# PWM_BoardSchem.net
KiCad netlist of a schematic drawn in Altium Designer
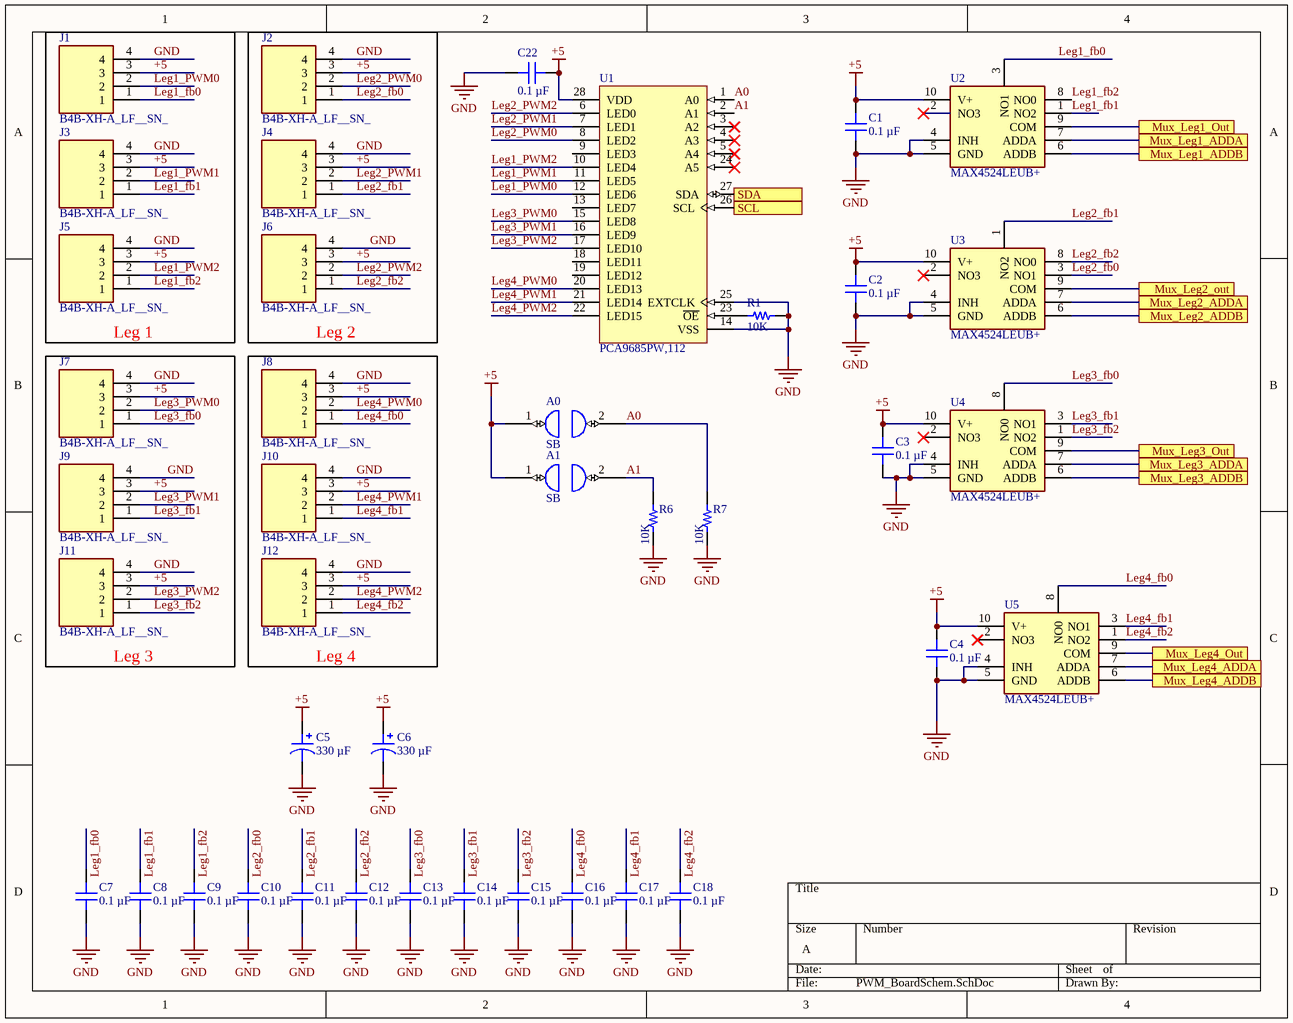
[diagram p0: PWM_BoardSchem.SchDoc]

(export (version "E")
  (design (tool "Eeschema 10.0.6"))
  (components
    (comp (ref "A0")
      (value "SB")
      (footprint "CAPC2010X06N")
      (description "Solder Bridge/0 ohm")
      (libsource (lib "Donados") (part "SB-Symbol-1"))
    )
    (comp (ref "A1")
      (value "SB")
      (footprint "CAPC2010X06N")
      (description "Solder Bridge/0 ohm")
      (libsource (lib "Donados") (part "SB-Symbol-1"))
    )
    (comp (ref "C1")
      (value "0.1 µF")
      (footprint "CAP 1206_3216 - 0.8MM")
      (description "CAP CER 0.1UF 50V Y5V 1206")
      (fields (field (name "PART NUMBER") "CC1206ZRY5V9BB104") (field (name "MANUFACTURER") "Yageo"))
      (libsource (lib "Celestial Altium Library - altium_library") (part "Capacitor"))
    )
    (comp (ref "C2")
      (value "0.1 µF")
      (footprint "CAP 1206_3216 - 0.8MM")
      (description "CAP CER 0.1UF 50V Y5V 1206")
      (fields (field (name "PART NUMBER") "CC1206ZRY5V9BB104") (field (name "MANUFACTURER") "Yageo"))
      (libsource (lib "Celestial Altium Library - altium_library") (part "Capacitor"))
    )
    (comp (ref "C3")
      (value "0.1 µF")
      (footprint "CAP 1206_3216 - 0.8MM")
      (description "CAP CER 0.1UF 50V Y5V 1206")
      (fields (field (name "PART NUMBER") "CC1206ZRY5V9BB104") (field (name "MANUFACTURER") "Yageo"))
      (libsource (lib "Celestial Altium Library - altium_library") (part "Capacitor"))
    )
    (comp (ref "C4")
      (value "0.1 µF")
      (footprint "CAP 1206_3216 - 0.8MM")
      (description "CAP CER 0.1UF 50V Y5V 1206")
      (fields (field (name "PART NUMBER") "CC1206ZRY5V9BB104") (field (name "MANUFACTURER") "Yageo"))
      (libsource (lib "Celestial Altium Library - altium_library") (part "Capacitor"))
    )
    (comp (ref "C5")
      (value "330 µF")
      (footprint "CAP TH ALPOLY D8.00mm S3.50mm H9.00mm")
      (description "CAP ALUM POLY 330UF 20% 16V T/H")
      (fields (field (name "PART NUMBER") "RL81C331MDN1KX") (field (name "MANUFACTURER") "Nichicon"))
      (libsource (lib "Celestial Altium Library - altium_library") (part "Polarised Capacitor"))
    )
    (comp (ref "C6")
      (value "330 µF")
      (footprint "CAP TH ALPOLY D8.00mm S3.50mm H9.00mm")
      (description "CAP ALUM POLY 330UF 20% 16V T/H")
      (fields (field (name "PART NUMBER") "RL81C331MDN1KX") (field (name "MANUFACTURER") "Nichicon"))
      (libsource (lib "Celestial Altium Library - altium_library") (part "Polarised Capacitor"))
    )
    (comp (ref "C7")
      (value "0.1 µF")
      (footprint "CAP 1206_3216 - 0.8MM")
      (description "CAP CER 0.1UF 50V Y5V 1206")
      (fields (field (name "PART NUMBER") "CC1206ZRY5V9BB104") (field (name "MANUFACTURER") "Yageo"))
      (libsource (lib "Celestial Altium Library - altium_library") (part "Capacitor"))
    )
    (comp (ref "C8")
      (value "0.1 µF")
      (footprint "CAP 1206_3216 - 0.8MM")
      (description "CAP CER 0.1UF 50V Y5V 1206")
      (fields (field (name "PART NUMBER") "CC1206ZRY5V9BB104") (field (name "MANUFACTURER") "Yageo"))
      (libsource (lib "Celestial Altium Library - altium_library") (part "Capacitor"))
    )
    (comp (ref "C9")
      (value "0.1 µF")
      (footprint "CAP 1206_3216 - 0.8MM")
      (description "CAP CER 0.1UF 50V Y5V 1206")
      (fields (field (name "PART NUMBER") "CC1206ZRY5V9BB104") (field (name "MANUFACTURER") "Yageo"))
      (libsource (lib "Celestial Altium Library - altium_library") (part "Capacitor"))
    )
    (comp (ref "C10")
      (value "0.1 µF")
      (footprint "CAP 1206_3216 - 0.8MM")
      (description "CAP CER 0.1UF 50V Y5V 1206")
      (fields (field (name "PART NUMBER") "CC1206ZRY5V9BB104") (field (name "MANUFACTURER") "Yageo"))
      (libsource (lib "Celestial Altium Library - altium_library") (part "Capacitor"))
    )
    (comp (ref "C11")
      (value "0.1 µF")
      (footprint "CAP 1206_3216 - 0.8MM")
      (description "CAP CER 0.1UF 50V Y5V 1206")
      (fields (field (name "PART NUMBER") "CC1206ZRY5V9BB104") (field (name "MANUFACTURER") "Yageo"))
      (libsource (lib "Celestial Altium Library - altium_library") (part "Capacitor"))
    )
    (comp (ref "C12")
      (value "0.1 µF")
      (footprint "CAP 1206_3216 - 0.8MM")
      (description "CAP CER 0.1UF 50V Y5V 1206")
      (fields (field (name "PART NUMBER") "CC1206ZRY5V9BB104") (field (name "MANUFACTURER") "Yageo"))
      (libsource (lib "Celestial Altium Library - altium_library") (part "Capacitor"))
    )
    (comp (ref "C13")
      (value "0.1 µF")
      (footprint "CAP 1206_3216 - 0.8MM")
      (description "CAP CER 0.1UF 50V Y5V 1206")
      (fields (field (name "PART NUMBER") "CC1206ZRY5V9BB104") (field (name "MANUFACTURER") "Yageo"))
      (libsource (lib "Celestial Altium Library - altium_library") (part "Capacitor"))
    )
    (comp (ref "C14")
      (value "0.1 µF")
      (footprint "CAP 1206_3216 - 0.8MM")
      (description "CAP CER 0.1UF 50V Y5V 1206")
      (fields (field (name "PART NUMBER") "CC1206ZRY5V9BB104") (field (name "MANUFACTURER") "Yageo"))
      (libsource (lib "Celestial Altium Library - altium_library") (part "Capacitor"))
    )
    (comp (ref "C15")
      (value "0.1 µF")
      (footprint "CAP 1206_3216 - 0.8MM")
      (description "CAP CER 0.1UF 50V Y5V 1206")
      (fields (field (name "PART NUMBER") "CC1206ZRY5V9BB104") (field (name "MANUFACTURER") "Yageo"))
      (libsource (lib "Celestial Altium Library - altium_library") (part "Capacitor"))
    )
    (comp (ref "C16")
      (value "0.1 µF")
      (footprint "CAP 1206_3216 - 0.8MM")
      (description "CAP CER 0.1UF 50V Y5V 1206")
      (fields (field (name "PART NUMBER") "CC1206ZRY5V9BB104") (field (name "MANUFACTURER") "Yageo"))
      (libsource (lib "Celestial Altium Library - altium_library") (part "Capacitor"))
    )
    (comp (ref "C17")
      (value "0.1 µF")
      (footprint "CAP 1206_3216 - 0.8MM")
      (description "CAP CER 0.1UF 50V Y5V 1206")
      (fields (field (name "PART NUMBER") "CC1206ZRY5V9BB104") (field (name "MANUFACTURER") "Yageo"))
      (libsource (lib "Celestial Altium Library - altium_library") (part "Capacitor"))
    )
    (comp (ref "C18")
      (value "0.1 µF")
      (footprint "CAP 1206_3216 - 0.8MM")
      (description "CAP CER 0.1UF 50V Y5V 1206")
      (fields (field (name "PART NUMBER") "CC1206ZRY5V9BB104") (field (name "MANUFACTURER") "Yageo"))
      (libsource (lib "Celestial Altium Library - altium_library") (part "Capacitor"))
    )
    (comp (ref "C22")
      (value "0.1 µF")
      (footprint "CAP 1206_3216 - 0.8MM")
      (description "CAP CER 0.1UF 50V Y5V 1206")
      (fields (field (name "PART NUMBER") "CC1206ZRY5V9BB104") (field (name "MANUFACTURER") "Yageo"))
      (libsource (lib "Celestial Altium Library - altium_library") (part "Capacitor"))
    )
    (comp (ref "J1")
      (value "B4B-XH-A_LF__SN_")
      (footprint "SamacSys:B4BXHALFSN")
      (description "Connector")
      (fields (field (name "MANUFACTURER_PART_NUMBER") "B4B-XH-A(LF)(SN)"))
      (libsource (lib "*") (part "B4B-XH-A_LF__SN_"))
    )
    (comp (ref "J2")
      (value "B4B-XH-A_LF__SN_")
      (footprint "SamacSys:B4BXHALFSN")
      (description "Connector")
      (fields (field (name "MANUFACTURER_PART_NUMBER") "B4B-XH-A(LF)(SN)"))
      (libsource (lib "*") (part "B4B-XH-A_LF__SN_"))
    )
    (comp (ref "J3")
      (value "B4B-XH-A_LF__SN_")
      (footprint "SamacSys:B4BXHALFSN")
      (description "Connector")
      (fields (field (name "MANUFACTURER_PART_NUMBER") "B4B-XH-A(LF)(SN)"))
      (libsource (lib "*") (part "B4B-XH-A_LF__SN_"))
    )
    (comp (ref "J4")
      (value "B4B-XH-A_LF__SN_")
      (footprint "SamacSys:B4BXHALFSN")
      (description "Connector")
      (fields (field (name "MANUFACTURER_PART_NUMBER") "B4B-XH-A(LF)(SN)"))
      (libsource (lib "*") (part "B4B-XH-A_LF__SN_"))
    )
    (comp (ref "J5")
      (value "B4B-XH-A_LF__SN_")
      (footprint "SamacSys:B4BXHALFSN")
      (description "Connector")
      (fields (field (name "MANUFACTURER_PART_NUMBER") "B4B-XH-A(LF)(SN)"))
      (libsource (lib "*") (part "B4B-XH-A_LF__SN_"))
    )
    (comp (ref "J6")
      (value "B4B-XH-A_LF__SN_")
      (footprint "SamacSys:B4BXHALFSN")
      (description "Connector")
      (fields (field (name "MANUFACTURER_PART_NUMBER") "B4B-XH-A(LF)(SN)"))
      (libsource (lib "*") (part "B4B-XH-A_LF__SN_"))
    )
    (comp (ref "J7")
      (value "B4B-XH-A_LF__SN_")
      (footprint "SamacSys:B4BXHALFSN")
      (description "Connector")
      (fields (field (name "MANUFACTURER_PART_NUMBER") "B4B-XH-A(LF)(SN)"))
      (libsource (lib "*") (part "B4B-XH-A_LF__SN_"))
    )
    (comp (ref "J8")
      (value "B4B-XH-A_LF__SN_")
      (footprint "SamacSys:B4BXHALFSN")
      (description "Connector")
      (fields (field (name "MANUFACTURER_PART_NUMBER") "B4B-XH-A(LF)(SN)"))
      (libsource (lib "*") (part "B4B-XH-A_LF__SN_"))
    )
    (comp (ref "J9")
      (value "B4B-XH-A_LF__SN_")
      (footprint "SamacSys:B4BXHALFSN")
      (description "Connector")
      (fields (field (name "MANUFACTURER_PART_NUMBER") "B4B-XH-A(LF)(SN)"))
      (libsource (lib "*") (part "B4B-XH-A_LF__SN_"))
    )
    (comp (ref "J10")
      (value "B4B-XH-A_LF__SN_")
      (footprint "SamacSys:B4BXHALFSN")
      (description "Connector")
      (fields (field (name "MANUFACTURER_PART_NUMBER") "B4B-XH-A(LF)(SN)"))
      (libsource (lib "*") (part "B4B-XH-A_LF__SN_"))
    )
    (comp (ref "J11")
      (value "B4B-XH-A_LF__SN_")
      (footprint "SamacSys:B4BXHALFSN")
      (description "Connector")
      (fields (field (name "MANUFACTURER_PART_NUMBER") "B4B-XH-A(LF)(SN)"))
      (libsource (lib "*") (part "B4B-XH-A_LF__SN_"))
    )
    (comp (ref "J12")
      (value "B4B-XH-A_LF__SN_")
      (footprint "SamacSys:B4BXHALFSN")
      (description "Connector")
      (fields (field (name "MANUFACTURER_PART_NUMBER") "B4B-XH-A(LF)(SN)"))
      (libsource (lib "*") (part "B4B-XH-A_LF__SN_"))
    )
    (comp (ref "R1")
      (value "10K")
      (footprint "RES 1206_3216")
      (description "RES SMD 10K OHM 1% 1/2W 1206")
      (fields (field (name "PART NUMBER") "ESR18EZPF1002") (field (name "MANUFACTURER") "Rohm Semiconductor"))
      (libsource (lib "Celestial Altium Library - altium_library") (part "Resistor"))
    )
    (comp (ref "R6")
      (value "10K")
      (footprint "RES 1206_3216")
      (description "RES SMD 10K OHM 1% 1/2W 1206")
      (fields (field (name "PART NUMBER") "ESR18EZPF1002") (field (name "MANUFACTURER") "Rohm Semiconductor"))
      (libsource (lib "Celestial Altium Library - altium_library") (part "Resistor"))
    )
    (comp (ref "R7")
      (value "10K")
      (footprint "RES 1206_3216")
      (description "RES SMD 10K OHM 1% 1/2W 1206")
      (fields (field (name "PART NUMBER") "ESR18EZPF1002") (field (name "MANUFACTURER") "Rohm Semiconductor"))
      (libsource (lib "Celestial Altium Library - altium_library") (part "Resistor"))
    )
    (comp (ref "U1")
      (value "PCA9685PW,112")
      (footprint "SOT361-1_V")
      (fields (field (name "PARTNUMBER") "PCA9685"))
      (libsource (lib "Altium Content Vault") (part "NXP-PCA9685-SOT361-1"))
    )
    (comp (ref "U2")
      (value "MAX4524LEUB+")
      (footprint "SamacSys:SOP50P490X110-10N")
      (description "Integrated Circuit")
      (fields (field (name "MOUSER PART NUMBER") "700-MAX4524LEUB+"))
      (libsource (lib "*") (part "MAX4524LEUB+"))
    )
    (comp (ref "U3")
      (value "MAX4524LEUB+")
      (footprint "SamacSys:SOP50P490X110-10N")
      (description "Integrated Circuit")
      (fields (field (name "MOUSER PART NUMBER") "700-MAX4524LEUB+"))
      (libsource (lib "") (part "MAX4524LEUB+_1"))
    )
    (comp (ref "U4")
      (value "MAX4524LEUB+")
      (footprint "SamacSys:SOP50P490X110-10N")
      (description "Integrated Circuit")
      (fields (field (name "MOUSER PART NUMBER") "700-MAX4524LEUB+"))
      (libsource (lib "") (part "MAX4524LEUB+_2"))
    )
    (comp (ref "U5")
      (value "MAX4524LEUB+")
      (footprint "SamacSys:SOP50P490X110-10N")
      (description "Integrated Circuit")
      (fields (field (name "MOUSER PART NUMBER") "700-MAX4524LEUB+"))
      (libsource (lib "") (part "MAX4524LEUB+_2"))
    )
  )
  (nets
    (net (code "1") (name "+5") (class "Default")
      (node (ref "A0") (pin "1") (pintype "bidirectional"))
      (node (ref "A1") (pin "1") (pintype "bidirectional"))
      (node (ref "C1") (pin "2") (pinfunction "2_2") (pintype "passive"))
      (node (ref "C2") (pin "2") (pinfunction "2_2") (pintype "passive"))
      (node (ref "C22") (pin "1") (pinfunction "1_1") (pintype "passive"))
      (node (ref "C3") (pin "2") (pinfunction "2_2") (pintype "passive"))
      (node (ref "C4") (pin "2") (pinfunction "2_2") (pintype "passive"))
      (node (ref "C5") (pin "1") (pinfunction "1_1") (pintype "passive"))
      (node (ref "C6") (pin "1") (pinfunction "1_1") (pintype "passive"))
      (node (ref "J1") (pin "3") (pinfunction "3_3") (pintype "passive"))
      (node (ref "J10") (pin "3") (pinfunction "3_3") (pintype "passive"))
      (node (ref "J11") (pin "3") (pinfunction "3_3") (pintype "passive"))
      (node (ref "J12") (pin "3") (pinfunction "3_3") (pintype "passive"))
      (node (ref "J2") (pin "3") (pinfunction "3_3") (pintype "passive"))
      (node (ref "J3") (pin "3") (pinfunction "3_3") (pintype "passive"))
      (node (ref "J4") (pin "3") (pinfunction "3_3") (pintype "passive"))
      (node (ref "J5") (pin "3") (pinfunction "3_3") (pintype "passive"))
      (node (ref "J6") (pin "3") (pinfunction "3_3") (pintype "passive"))
      (node (ref "J7") (pin "3") (pinfunction "3_3") (pintype "passive"))
      (node (ref "J8") (pin "3") (pinfunction "3_3") (pintype "passive"))
      (node (ref "J9") (pin "3") (pinfunction "3_3") (pintype "passive"))
      (node (ref "U1") (pin "28") (pinfunction "VDD_28") (pintype "power_in"))
      (node (ref "U2") (pin "10") (pinfunction "V+_10") (pintype "passive"))
      (node (ref "U3") (pin "10") (pinfunction "V+_10") (pintype "passive"))
      (node (ref "U4") (pin "10") (pinfunction "V+_10") (pintype "passive"))
      (node (ref "U5") (pin "10") (pinfunction "V+_10") (pintype "passive"))
    )
    (net (code "2") (name "/A0") (class "Default")
      (node (ref "A0") (pin "2") (pintype "bidirectional"))
      (node (ref "R7") (pin "2") (pinfunction "2_2") (pintype "passive"))
      (node (ref "U1") (pin "1") (pinfunction "A0_1") (pintype "input"))
    )
    (net (code "3") (name "/A1") (class "Default")
      (node (ref "A1") (pin "2") (pintype "bidirectional"))
      (node (ref "R6") (pin "2") (pinfunction "2_2") (pintype "passive"))
      (node (ref "U1") (pin "2") (pinfunction "A1_2") (pintype "input"))
    )
    (net (code "4") (name "/Leg1_PWM0") (class "Default")
      (node (ref "J1") (pin "2") (pinfunction "2_2") (pintype "passive"))
      (node (ref "U1") (pin "12") (pinfunction "LED6_12") (pintype "tri_state"))
    )
    (net (code "5") (name "/Leg1_PWM1") (class "Default")
      (node (ref "J3") (pin "2") (pinfunction "2_2") (pintype "passive"))
      (node (ref "U1") (pin "11") (pinfunction "LED5_11") (pintype "tri_state"))
    )
    (net (code "6") (name "/Leg1_PWM2") (class "Default")
      (node (ref "J5") (pin "2") (pinfunction "2_2") (pintype "passive"))
      (node (ref "U1") (pin "10") (pinfunction "LED4_10") (pintype "tri_state"))
    )
    (net (code "7") (name "/Leg1_fb0") (class "Default")
      (node (ref "C7") (pin "2") (pinfunction "2_2") (pintype "passive"))
      (node (ref "J1") (pin "1") (pinfunction "1_1") (pintype "passive"))
      (node (ref "U2") (pin "3") (pinfunction "NO1_3") (pintype "passive"))
    )
    (net (code "8") (name "/Leg1_fb1") (class "Default")
      (node (ref "C8") (pin "2") (pinfunction "2_2") (pintype "passive"))
      (node (ref "J3") (pin "1") (pinfunction "1_1") (pintype "passive"))
      (node (ref "U2") (pin "1") (pinfunction "NO2_1") (pintype "passive"))
    )
    (net (code "9") (name "/Leg1_fb2") (class "Default")
      (node (ref "C9") (pin "2") (pinfunction "2_2") (pintype "passive"))
      (node (ref "J5") (pin "1") (pinfunction "1_1") (pintype "passive"))
      (node (ref "U2") (pin "8") (pinfunction "NO0_8") (pintype "passive"))
    )
    (net (code "10") (name "/Leg2_PWM0") (class "Default")
      (node (ref "J2") (pin "2") (pinfunction "2_2") (pintype "passive"))
      (node (ref "U1") (pin "8") (pinfunction "LED2_8") (pintype "tri_state"))
    )
    (net (code "11") (name "/Leg2_PWM1") (class "Default")
      (node (ref "J4") (pin "2") (pinfunction "2_2") (pintype "passive"))
      (node (ref "U1") (pin "7") (pinfunction "LED1_7") (pintype "tri_state"))
    )
    (net (code "12") (name "/Leg2_PWM2") (class "Default")
      (node (ref "J6") (pin "2") (pinfunction "2_2") (pintype "passive"))
      (node (ref "U1") (pin "6") (pinfunction "LED0_6") (pintype "tri_state"))
    )
    (net (code "13") (name "/Leg2_fb0") (class "Default")
      (node (ref "C10") (pin "2") (pinfunction "2_2") (pintype "passive"))
      (node (ref "J2") (pin "1") (pinfunction "1_1") (pintype "passive"))
      (node (ref "U3") (pin "3") (pinfunction "NO1_3") (pintype "passive"))
    )
    (net (code "14") (name "/Leg2_fb1") (class "Default")
      (node (ref "C11") (pin "2") (pinfunction "2_2") (pintype "passive"))
      (node (ref "J4") (pin "1") (pinfunction "1_1") (pintype "passive"))
      (node (ref "U3") (pin "1") (pinfunction "NO2_1") (pintype "passive"))
    )
    (net (code "15") (name "/Leg2_fb2") (class "Default")
      (node (ref "C12") (pin "2") (pinfunction "2_2") (pintype "passive"))
      (node (ref "J6") (pin "1") (pinfunction "1_1") (pintype "passive"))
      (node (ref "U3") (pin "8") (pinfunction "NO0_8") (pintype "passive"))
    )
    (net (code "16") (name "/Leg3_PWM0") (class "Default")
      (node (ref "J7") (pin "2") (pinfunction "2_2") (pintype "passive"))
      (node (ref "U1") (pin "15") (pinfunction "LED8_15") (pintype "tri_state"))
    )
    (net (code "17") (name "/Leg3_PWM1") (class "Default")
      (node (ref "J9") (pin "2") (pinfunction "2_2") (pintype "passive"))
      (node (ref "U1") (pin "16") (pinfunction "LED9_16") (pintype "tri_state"))
    )
    (net (code "18") (name "/Leg3_PWM2") (class "Default")
      (node (ref "J11") (pin "2") (pinfunction "2_2") (pintype "passive"))
      (node (ref "U1") (pin "17") (pinfunction "LED10_17") (pintype "tri_state"))
    )
    (net (code "19") (name "/Leg3_fb0") (class "Default")
      (node (ref "C13") (pin "2") (pinfunction "2_2") (pintype "passive"))
      (node (ref "J7") (pin "1") (pinfunction "1_1") (pintype "passive"))
      (node (ref "U4") (pin "8") (pinfunction "NO0_8") (pintype "passive"))
    )
    (net (code "20") (name "/Leg3_fb1") (class "Default")
      (node (ref "C14") (pin "2") (pinfunction "2_2") (pintype "passive"))
      (node (ref "J9") (pin "1") (pinfunction "1_1") (pintype "passive"))
      (node (ref "U4") (pin "3") (pinfunction "NO1_3") (pintype "passive"))
    )
    (net (code "21") (name "/Leg3_fb2") (class "Default")
      (node (ref "C15") (pin "2") (pinfunction "2_2") (pintype "passive"))
      (node (ref "J11") (pin "1") (pinfunction "1_1") (pintype "passive"))
      (node (ref "U4") (pin "1") (pinfunction "NO2_1") (pintype "passive"))
    )
    (net (code "22") (name "/Leg4_PWM0") (class "Default")
      (node (ref "J8") (pin "2") (pinfunction "2_2") (pintype "passive"))
      (node (ref "U1") (pin "20") (pinfunction "LED13_20") (pintype "tri_state"))
    )
    (net (code "23") (name "/Leg4_PWM1") (class "Default")
      (node (ref "J10") (pin "2") (pinfunction "2_2") (pintype "passive"))
      (node (ref "U1") (pin "21") (pinfunction "LED14_21") (pintype "tri_state"))
    )
    (net (code "24") (name "/Leg4_PWM2") (class "Default")
      (node (ref "J12") (pin "2") (pinfunction "2_2") (pintype "passive"))
      (node (ref "U1") (pin "22") (pinfunction "LED15_22") (pintype "tri_state"))
    )
    (net (code "25") (name "/Leg4_fb0") (class "Default")
      (node (ref "C16") (pin "2") (pinfunction "2_2") (pintype "passive"))
      (node (ref "J8") (pin "1") (pinfunction "1_1") (pintype "passive"))
      (node (ref "U5") (pin "8") (pinfunction "NO0_8") (pintype "passive"))
    )
    (net (code "26") (name "/Leg4_fb1") (class "Default")
      (node (ref "C17") (pin "2") (pinfunction "2_2") (pintype "passive"))
      (node (ref "J10") (pin "1") (pinfunction "1_1") (pintype "passive"))
      (node (ref "U5") (pin "3") (pinfunction "NO1_3") (pintype "passive"))
    )
    (net (code "27") (name "/Leg4_fb2") (class "Default")
      (node (ref "C18") (pin "2") (pinfunction "2_2") (pintype "passive"))
      (node (ref "J12") (pin "1") (pinfunction "1_1") (pintype "passive"))
      (node (ref "U5") (pin "1") (pinfunction "NO2_1") (pintype "passive"))
    )
    (net (code "28") (name "/Mux_Leg1_ADDA") (class "Default")
      (node (ref "U2") (pin "7") (pinfunction "ADDA_7") (pintype "passive"))
    )
    (net (code "29") (name "/Mux_Leg1_ADDB") (class "Default")
      (node (ref "U2") (pin "6") (pinfunction "ADDB_6") (pintype "passive"))
    )
    (net (code "30") (name "/Mux_Leg1_Out") (class "Default")
      (node (ref "U2") (pin "9") (pinfunction "COM_9") (pintype "passive"))
    )
    (net (code "31") (name "/Mux_Leg2_ADDA") (class "Default")
      (node (ref "U3") (pin "7") (pinfunction "ADDA_7") (pintype "passive"))
    )
    (net (code "32") (name "/Mux_Leg2_ADDB") (class "Default")
      (node (ref "U3") (pin "6") (pinfunction "ADDB_6") (pintype "passive"))
    )
    (net (code "33") (name "/Mux_Leg2_out") (class "Default")
      (node (ref "U3") (pin "9") (pinfunction "COM_9") (pintype "passive"))
    )
    (net (code "34") (name "/Mux_Leg3_ADDA") (class "Default")
      (node (ref "U4") (pin "7") (pinfunction "ADDA_7") (pintype "passive"))
    )
    (net (code "35") (name "/Mux_Leg3_ADDB") (class "Default")
      (node (ref "U4") (pin "6") (pinfunction "ADDB_6") (pintype "passive"))
    )
    (net (code "36") (name "/Mux_Leg3_Out") (class "Default")
      (node (ref "U4") (pin "9") (pinfunction "COM_9") (pintype "passive"))
    )
    (net (code "37") (name "/Mux_Leg4_ADDA") (class "Default")
      (node (ref "U5") (pin "7") (pinfunction "ADDA_7") (pintype "passive"))
    )
    (net (code "38") (name "/Mux_Leg4_ADDB") (class "Default")
      (node (ref "U5") (pin "6") (pinfunction "ADDB_6") (pintype "passive"))
    )
    (net (code "39") (name "/Mux_Leg4_Out") (class "Default")
      (node (ref "U5") (pin "9") (pinfunction "COM_9") (pintype "passive"))
    )
    (net (code "40") (name "/SCL") (class "Default")
      (node (ref "U1") (pin "26") (pinfunction "SCL_26") (pintype "input"))
    )
    (net (code "41") (name "/SDA") (class "Default")
      (node (ref "U1") (pin "27") (pinfunction "SDA_27") (pintype "bidirectional"))
    )
    (net (code "42") (name "GND") (class "Default")
      (node (ref "C1") (pin "1") (pinfunction "1_1") (pintype "passive"))
      (node (ref "C10") (pin "1") (pinfunction "1_1") (pintype "passive"))
      (node (ref "C11") (pin "1") (pinfunction "1_1") (pintype "passive"))
      (node (ref "C12") (pin "1") (pinfunction "1_1") (pintype "passive"))
      (node (ref "C13") (pin "1") (pinfunction "1_1") (pintype "passive"))
      (node (ref "C14") (pin "1") (pinfunction "1_1") (pintype "passive"))
      (node (ref "C15") (pin "1") (pinfunction "1_1") (pintype "passive"))
      (node (ref "C16") (pin "1") (pinfunction "1_1") (pintype "passive"))
      (node (ref "C17") (pin "1") (pinfunction "1_1") (pintype "passive"))
      (node (ref "C18") (pin "1") (pinfunction "1_1") (pintype "passive"))
      (node (ref "C2") (pin "1") (pinfunction "1_1") (pintype "passive"))
      (node (ref "C22") (pin "2") (pinfunction "2_2") (pintype "passive"))
      (node (ref "C3") (pin "1") (pinfunction "1_1") (pintype "passive"))
      (node (ref "C4") (pin "1") (pinfunction "1_1") (pintype "passive"))
      (node (ref "C5") (pin "2") (pinfunction "2_2") (pintype "passive"))
      (node (ref "C6") (pin "2") (pinfunction "2_2") (pintype "passive"))
      (node (ref "C7") (pin "1") (pinfunction "1_1") (pintype "passive"))
      (node (ref "C8") (pin "1") (pinfunction "1_1") (pintype "passive"))
      (node (ref "C9") (pin "1") (pinfunction "1_1") (pintype "passive"))
      (node (ref "J1") (pin "4") (pinfunction "4_4") (pintype "passive"))
      (node (ref "J10") (pin "4") (pinfunction "4_4") (pintype "passive"))
      (node (ref "J11") (pin "4") (pinfunction "4_4") (pintype "passive"))
      (node (ref "J12") (pin "4") (pinfunction "4_4") (pintype "passive"))
      (node (ref "J2") (pin "4") (pinfunction "4_4") (pintype "passive"))
      (node (ref "J3") (pin "4") (pinfunction "4_4") (pintype "passive"))
      (node (ref "J4") (pin "4") (pinfunction "4_4") (pintype "passive"))
      (node (ref "J5") (pin "4") (pinfunction "4_4") (pintype "passive"))
      (node (ref "J6") (pin "4") (pinfunction "4_4") (pintype "passive"))
      (node (ref "J7") (pin "4") (pinfunction "4_4") (pintype "passive"))
      (node (ref "J8") (pin "4") (pinfunction "4_4") (pintype "passive"))
      (node (ref "J9") (pin "4") (pinfunction "4_4") (pintype "passive"))
      (node (ref "R1") (pin "2") (pinfunction "2_2") (pintype "passive"))
      (node (ref "R6") (pin "1") (pinfunction "1_1") (pintype "passive"))
      (node (ref "R7") (pin "1") (pinfunction "1_1") (pintype "passive"))
      (node (ref "U1") (pin "14") (pinfunction "VSS_14") (pintype "power_in"))
      (node (ref "U1") (pin "25") (pinfunction "EXTCLK_25") (pintype "input"))
      (node (ref "U2") (pin "4") (pinfunction "INH_4") (pintype "passive"))
      (node (ref "U2") (pin "5") (pinfunction "GND_5") (pintype "passive"))
      (node (ref "U3") (pin "4") (pinfunction "INH_4") (pintype "passive"))
      (node (ref "U3") (pin "5") (pinfunction "GND_5") (pintype "passive"))
      (node (ref "U4") (pin "4") (pinfunction "INH_4") (pintype "passive"))
      (node (ref "U4") (pin "5") (pinfunction "GND_5") (pintype "passive"))
      (node (ref "U5") (pin "4") (pinfunction "INH_4") (pintype "passive"))
      (node (ref "U5") (pin "5") (pinfunction "GND_5") (pintype "passive"))
    )
    (net (code "43") (name "Net-(U1-~{OE})") (class "Default")
      (node (ref "R1") (pin "1") (pinfunction "1_1") (pintype "passive"))
      (node (ref "U1") (pin "23") (pinfunction "~{OE}_23") (pintype "input"))
    )
    (net (code "44") (name "unconnected-(U1-A2-Pad3)") (class "Default")
      (node (ref "U1") (pin "3") (pinfunction "A2_3") (pintype "input+no_connect"))
    )
    (net (code "45") (name "unconnected-(U1-A3-Pad4)") (class "Default")
      (node (ref "U1") (pin "4") (pinfunction "A3_4") (pintype "input+no_connect"))
    )
    (net (code "46") (name "unconnected-(U1-A4-Pad5)") (class "Default")
      (node (ref "U1") (pin "5") (pinfunction "A4_5") (pintype "input+no_connect"))
    )
    (net (code "47") (name "unconnected-(U1-A5-Pad24)") (class "Default")
      (node (ref "U1") (pin "24") (pinfunction "A5_24") (pintype "input+no_connect"))
    )
    (net (code "48") (name "unconnected-(U1-LED3-Pad9)") (class "Default")
      (node (ref "U1") (pin "9") (pinfunction "LED3_9") (pintype "tri_state"))
    )
    (net (code "49") (name "unconnected-(U1-LED7-Pad13)") (class "Default")
      (node (ref "U1") (pin "13") (pinfunction "LED7_13") (pintype "tri_state"))
    )
    (net (code "50") (name "unconnected-(U1-LED11-Pad18)") (class "Default")
      (node (ref "U1") (pin "18") (pinfunction "LED11_18") (pintype "tri_state"))
    )
    (net (code "51") (name "unconnected-(U1-LED12-Pad19)") (class "Default")
      (node (ref "U1") (pin "19") (pinfunction "LED12_19") (pintype "tri_state"))
    )
    (net (code "52") (name "unconnected-(U2-NO3-Pad2)") (class "Default")
      (node (ref "U2") (pin "2") (pinfunction "NO3_2") (pintype "passive+no_connect"))
    )
    (net (code "53") (name "unconnected-(U3-NO3-Pad2)") (class "Default")
      (node (ref "U3") (pin "2") (pinfunction "NO3_2") (pintype "passive+no_connect"))
    )
    (net (code "54") (name "unconnected-(U4-NO3-Pad2)") (class "Default")
      (node (ref "U4") (pin "2") (pinfunction "NO3_2") (pintype "passive+no_connect"))
    )
    (net (code "55") (name "unconnected-(U5-NO3-Pad2)") (class "Default")
      (node (ref "U5") (pin "2") (pinfunction "NO3_2") (pintype "passive+no_connect"))
    )
  )
)
